# rapidshark-lipo-sensor-mk-2_3.net
KiCad netlist of a schematic drawn in EAGLE
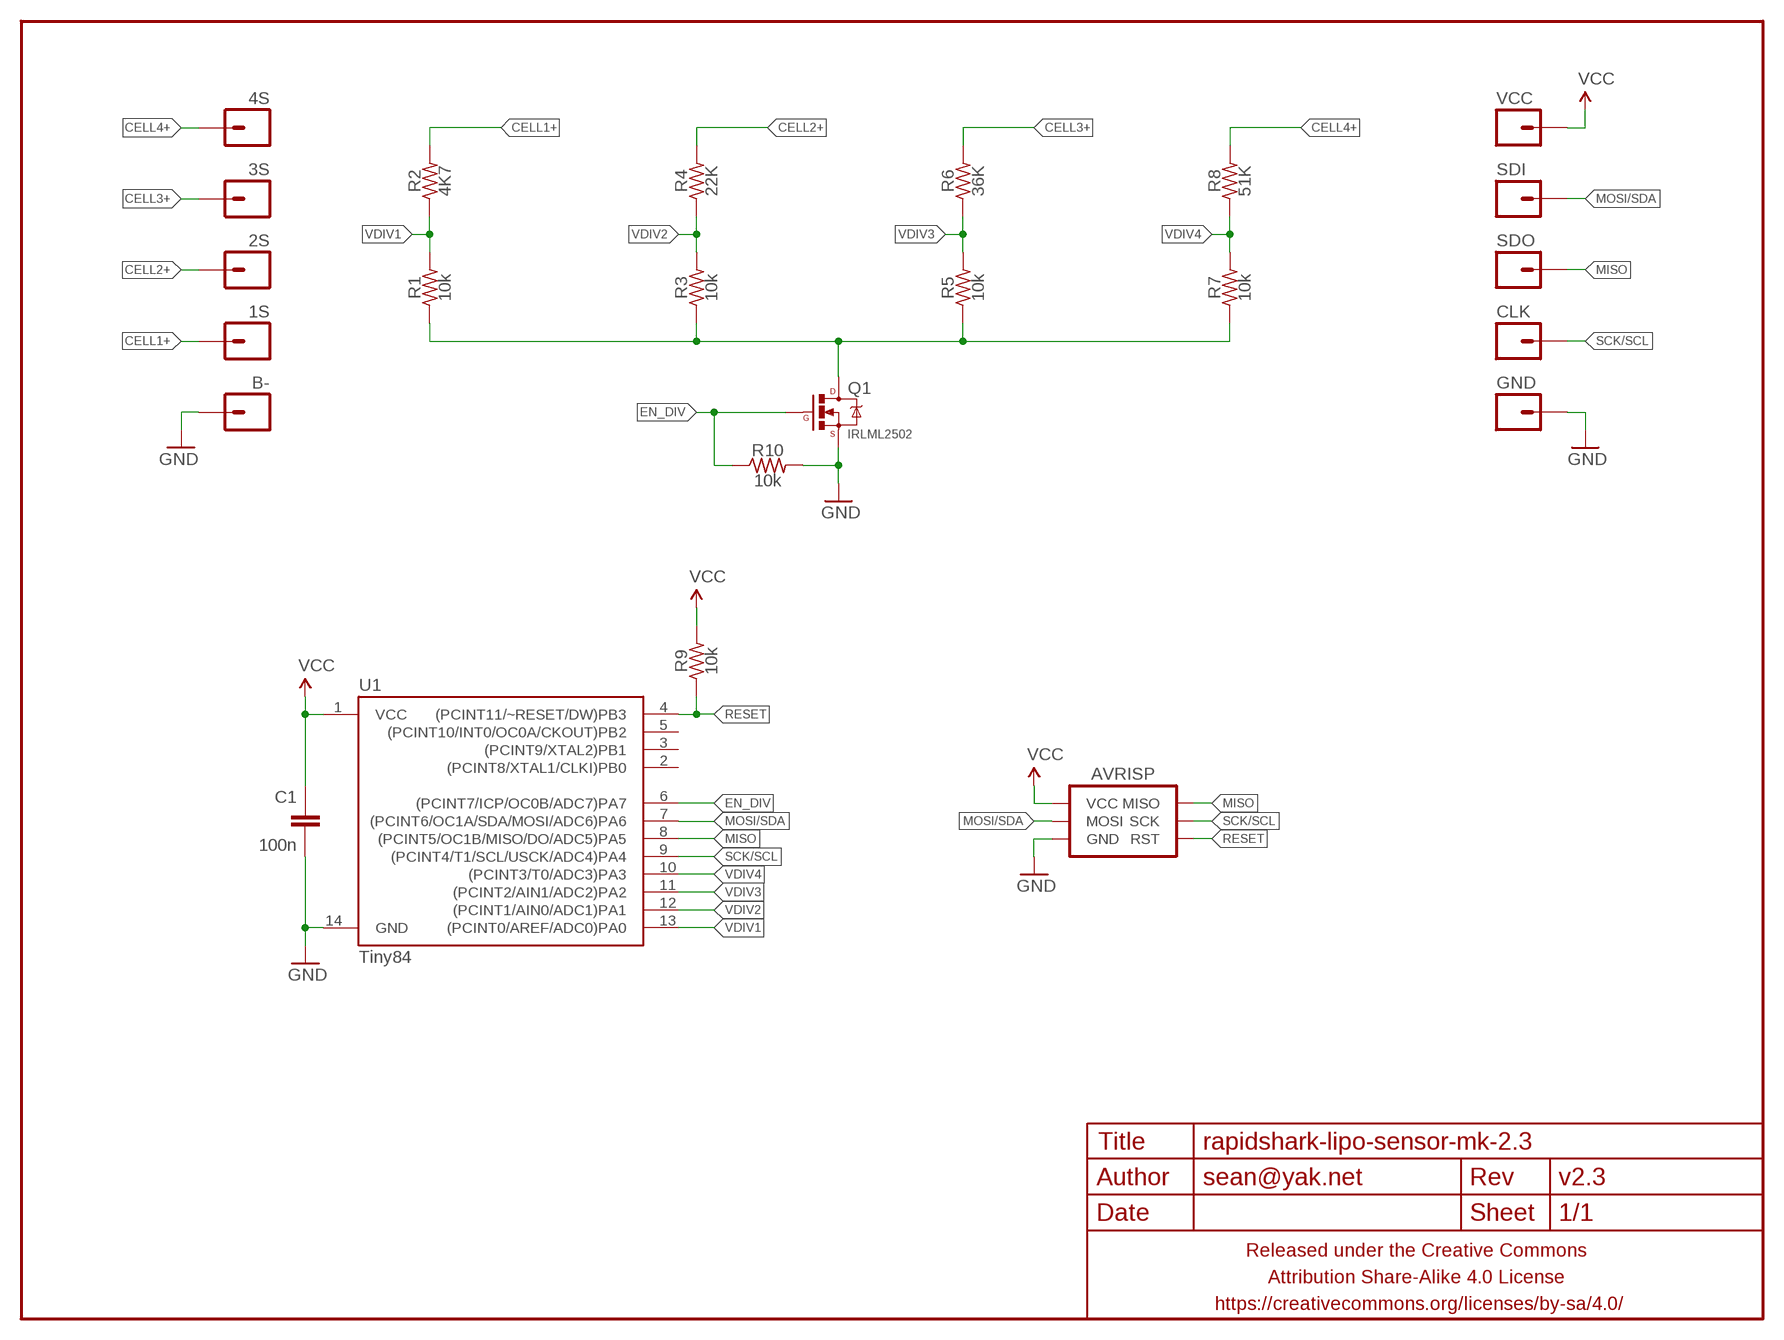
[diagram p0: schematic, sheet 1]

(export (version "E")
  (design (tool "Eeschema 10.0.6"))
  (components
    (comp (ref "1S")
      (value "M01PTH-0.9MM")
      (footprint "eagle-import:1X01-0.9MM")
      (libsource (lib "eagle-import") (part "M01PTH-0.9MM"))
    )
    (comp (ref "2S")
      (value "M01PTH-0.9MM")
      (footprint "eagle-import:1X01-0.9MM")
      (libsource (lib "eagle-import") (part "M01PTH-0.9MM"))
    )
    (comp (ref "3S")
      (value "M01PTH-0.9MM")
      (footprint "eagle-import:1X01-0.9MM")
      (libsource (lib "eagle-import") (part "M01PTH-0.9MM"))
    )
    (comp (ref "4S")
      (value "M01PTH-0.9MM")
      (footprint "eagle-import:1X01-0.9MM")
      (libsource (lib "eagle-import") (part "M01PTH-0.9MM"))
    )
    (comp (ref "AVRISP")
      (value "AVR_SPI_PRG_6TESTPOINTS")
      (footprint "eagle-import:2X3_TEST_POINTS")
      (libsource (lib "eagle-import") (part "AVR_SPI_PRG_6TESTPOINTS"))
    )
    (comp (ref "B-")
      (value "M01PTH-0.9MM")
      (footprint "eagle-import:1X01-0.9MM")
      (libsource (lib "eagle-import") (part "M01PTH-0.9MM"))
    )
    (comp (ref "C1")
      (value "100n")
      (footprint "eagle-import:C0603-TIGHTER")
      (libsource (lib "eagle-import") (part "CAPACITOR-CERAMICC0603-TIGHTER"))
    )
    (comp (ref "CLK")
      (value "M01PTH-0.9MM")
      (footprint "eagle-import:1X01-0.9MM")
      (libsource (lib "eagle-import") (part "M01PTH-0.9MM"))
    )
    (comp (ref "FRAME1")
      (value "FRAME-LETTERNO_PACKAGE")
      (footprint "eagle-import:DUMMY")
      (fields (field (name "DESIGNER") "sean@yak.net") (field (name "VERSION") "v2.3"))
      (libsource (lib "eagle-import") (part "FRAME-LETTERNO_PACKAGE"))
    )
    (comp (ref "GND")
      (value "M01PTH-0.9MM")
      (footprint "eagle-import:1X01-0.9MM")
      (libsource (lib "eagle-import") (part "M01PTH-0.9MM"))
    )
    (comp (ref "Q1")
      (value "IRLML2502")
      (footprint "eagle-import:SOT23")
      (libsource (lib "eagle-import") (part "MOSFET-NCHANNELIRLML2502"))
    )
    (comp (ref "R1")
      (value "10k")
      (footprint "eagle-import:R0603-TIGHTER")
      (libsource (lib "eagle-import") (part "RESISTORR0603-TIGHTER"))
    )
    (comp (ref "R2")
      (value "4K7")
      (footprint "eagle-import:R0603-TIGHTER")
      (libsource (lib "eagle-import") (part "RESISTORR0603-TIGHTER"))
    )
    (comp (ref "R3")
      (value "10k")
      (footprint "eagle-import:R0603-TIGHTER")
      (libsource (lib "eagle-import") (part "RESISTORR0603-TIGHTER"))
    )
    (comp (ref "R4")
      (value "22K")
      (footprint "eagle-import:R0603-TIGHTER")
      (libsource (lib "eagle-import") (part "RESISTORR0603-TIGHTER"))
    )
    (comp (ref "R5")
      (value "10k")
      (footprint "eagle-import:R0603-TIGHTER")
      (libsource (lib "eagle-import") (part "RESISTORR0603-TIGHTER"))
    )
    (comp (ref "R6")
      (value "36K")
      (footprint "eagle-import:R0603-TIGHTER")
      (libsource (lib "eagle-import") (part "RESISTORR0603-TIGHTER"))
    )
    (comp (ref "R7")
      (value "10k")
      (footprint "eagle-import:R0603-TIGHTER")
      (libsource (lib "eagle-import") (part "RESISTORR0603-TIGHTER"))
    )
    (comp (ref "R8")
      (value "51K")
      (footprint "eagle-import:R0603-TIGHTER")
      (libsource (lib "eagle-import") (part "RESISTORR0603-TIGHTER"))
    )
    (comp (ref "R9")
      (value "10k")
      (footprint "eagle-import:R0603-TIGHTER")
      (libsource (lib "eagle-import") (part "RESISTORR0603-TIGHTER"))
    )
    (comp (ref "R10")
      (value "10k")
      (footprint "eagle-import:R0603-TIGHTER")
      (libsource (lib "eagle-import") (part "RESISTORR0603-TIGHTER"))
    )
    (comp (ref "SDI")
      (value "M01PTH-0.9MM")
      (footprint "eagle-import:1X01-0.9MM")
      (libsource (lib "eagle-import") (part "M01PTH-0.9MM"))
    )
    (comp (ref "SDO")
      (value "M01PTH-0.9MM")
      (footprint "eagle-import:1X01-0.9MM")
      (libsource (lib "eagle-import") (part "M01PTH-0.9MM"))
    )
    (comp (ref "U1")
      (value "Tiny84")
      (footprint "eagle-import:SO14")
      (libsource (lib "eagle-import") (part "ATTINY84"))
    )
    (comp (ref "VCC")
      (value "M01PTH-0.9MM")
      (footprint "eagle-import:1X01-0.9MM")
      (libsource (lib "eagle-import") (part "M01PTH-0.9MM"))
    )
  )
  (nets
    (net (code "1") (name "CELL1+") (class "Default")
      (node (ref "1S") (pin "1") (pinfunction "1_1") (pintype "passive"))
      (node (ref "R2") (pin "2") (pinfunction "2_2") (pintype "passive"))
    )
    (net (code "2") (name "CELL2+") (class "Default")
      (node (ref "2S") (pin "1") (pinfunction "1_1") (pintype "passive"))
      (node (ref "R4") (pin "2") (pinfunction "2_2") (pintype "passive"))
    )
    (net (code "3") (name "CELL3+") (class "Default")
      (node (ref "3S") (pin "1") (pinfunction "1_1") (pintype "passive"))
      (node (ref "R6") (pin "2") (pinfunction "2_2") (pintype "passive"))
    )
    (net (code "4") (name "CELL4+") (class "Default")
      (node (ref "4S") (pin "1") (pinfunction "1_1") (pintype "passive"))
      (node (ref "R8") (pin "2") (pinfunction "2_2") (pintype "passive"))
    )
    (net (code "5") (name "EN_DIV") (class "Default")
      (node (ref "Q1") (pin "1") (pinfunction "G_1") (pintype "passive"))
      (node (ref "R10") (pin "1") (pinfunction "1_1") (pintype "passive"))
      (node (ref "U1") (pin "6") (pinfunction "(PCINT7/ICP/OC0B/ADC7)PA7_6") (pintype "bidirectional"))
    )
    (net (code "6") (name "GND") (class "Default")
      (node (ref "AVRISP") (pin "6") (pinfunction "GND_6") (pintype "passive"))
      (node (ref "B-") (pin "1") (pinfunction "1_1") (pintype "passive"))
      (node (ref "C1") (pin "2") (pinfunction "2_2") (pintype "passive"))
      (node (ref "GND") (pin "1") (pinfunction "1_1") (pintype "passive"))
      (node (ref "Q1") (pin "2") (pinfunction "S_2") (pintype "passive"))
      (node (ref "R10") (pin "2") (pinfunction "2_2") (pintype "passive"))
      (node (ref "U1") (pin "14") (pinfunction "GND_14") (pintype "bidirectional"))
    )
    (net (code "7") (name "MISO") (class "Default")
      (node (ref "AVRISP") (pin "1") (pinfunction "MISO_1") (pintype "passive"))
      (node (ref "SDO") (pin "1") (pinfunction "1_1") (pintype "passive"))
      (node (ref "U1") (pin "8") (pinfunction "(PCINT5/OC1B/MISO/DO/ADC5)PA5_8") (pintype "bidirectional"))
    )
    (net (code "8") (name "MOSI{slash}SDA") (class "Default")
      (node (ref "AVRISP") (pin "4") (pinfunction "MOSI_4") (pintype "passive"))
      (node (ref "SDI") (pin "1") (pinfunction "1_1") (pintype "passive"))
      (node (ref "U1") (pin "7") (pinfunction "(PCINT6/OC1A/SDA/MOSI/ADC6)PA6_7") (pintype "bidirectional"))
    )
    (net (code "9") (name "Net-(Q1-D)") (class "Default")
      (node (ref "Q1") (pin "3") (pinfunction "D_3") (pintype "passive"))
      (node (ref "R1") (pin "1") (pinfunction "1_1") (pintype "passive"))
      (node (ref "R3") (pin "1") (pinfunction "1_1") (pintype "passive"))
      (node (ref "R5") (pin "1") (pinfunction "1_1") (pintype "passive"))
      (node (ref "R7") (pin "1") (pinfunction "1_1") (pintype "passive"))
    )
    (net (code "10") (name "RESET") (class "Default")
      (node (ref "AVRISP") (pin "5") (pinfunction "RST_5") (pintype "passive"))
      (node (ref "R9") (pin "1") (pinfunction "1_1") (pintype "passive"))
      (node (ref "U1") (pin "4") (pinfunction "(PCINT11/~{RESET/DW})PB3_4") (pintype "bidirectional"))
    )
    (net (code "11") (name "SCK{slash}SCL") (class "Default")
      (node (ref "AVRISP") (pin "3") (pinfunction "SCK_3") (pintype "passive"))
      (node (ref "CLK") (pin "1") (pinfunction "1_1") (pintype "passive"))
      (node (ref "U1") (pin "9") (pinfunction "(PCINT4/T1/SCL/USCK/ADC4)PA4_9") (pintype "bidirectional"))
    )
    (net (code "12") (name "VCC") (class "Default")
      (node (ref "AVRISP") (pin "2") (pinfunction "VCC_2") (pintype "passive"))
      (node (ref "C1") (pin "1") (pinfunction "1_1") (pintype "passive"))
      (node (ref "R9") (pin "2") (pinfunction "2_2") (pintype "passive"))
      (node (ref "U1") (pin "1") (pinfunction "VCC_1") (pintype "bidirectional"))
      (node (ref "VCC") (pin "1") (pinfunction "1_1") (pintype "passive"))
    )
    (net (code "13") (name "VDIV1") (class "Default")
      (node (ref "R1") (pin "2") (pinfunction "2_2") (pintype "passive"))
      (node (ref "R2") (pin "1") (pinfunction "1_1") (pintype "passive"))
      (node (ref "U1") (pin "13") (pinfunction "(PCINT0/AREF/ADC0)PA0_13") (pintype "bidirectional"))
    )
    (net (code "14") (name "VDIV2") (class "Default")
      (node (ref "R3") (pin "2") (pinfunction "2_2") (pintype "passive"))
      (node (ref "R4") (pin "1") (pinfunction "1_1") (pintype "passive"))
      (node (ref "U1") (pin "12") (pinfunction "(PCINT1/AIN0/ADC1)PA1_12") (pintype "bidirectional"))
    )
    (net (code "15") (name "VDIV3") (class "Default")
      (node (ref "R5") (pin "2") (pinfunction "2_2") (pintype "passive"))
      (node (ref "R6") (pin "1") (pinfunction "1_1") (pintype "passive"))
      (node (ref "U1") (pin "11") (pinfunction "(PCINT2/AIN1/ADC2)PA2_11") (pintype "bidirectional"))
    )
    (net (code "16") (name "VDIV4") (class "Default")
      (node (ref "R7") (pin "2") (pinfunction "2_2") (pintype "passive"))
      (node (ref "R8") (pin "1") (pinfunction "1_1") (pintype "passive"))
      (node (ref "U1") (pin "10") (pinfunction "(PCINT3/T0/ADC3)PA3_10") (pintype "bidirectional"))
    )
    (net (code "17") (name "unconnected-(U1-(PCINT8{slash}XTAL1{slash}CLKI)PB0-Pad2)") (class "Default")
      (node (ref "U1") (pin "2") (pinfunction "(PCINT8/XTAL1/CLKI)PB0_2") (pintype "bidirectional"))
    )
    (net (code "18") (name "unconnected-(U1-(PCINT9{slash}XTAL2)PB1-Pad3)") (class "Default")
      (node (ref "U1") (pin "3") (pinfunction "(PCINT9/XTAL2)PB1_3") (pintype "bidirectional"))
    )
    (net (code "19") (name "unconnected-(U1-(PCINT10{slash}INT0{slash}OC0A{slash}CKOUT)PB2-Pad5)") (class "Default")
      (node (ref "U1") (pin "5") (pinfunction "(PCINT10/INT0/OC0A/CKOUT)PB2_5") (pintype "bidirectional"))
    )
  )
)
